# design.net
KiCad netlist of a schematic drawn in Altium Designer
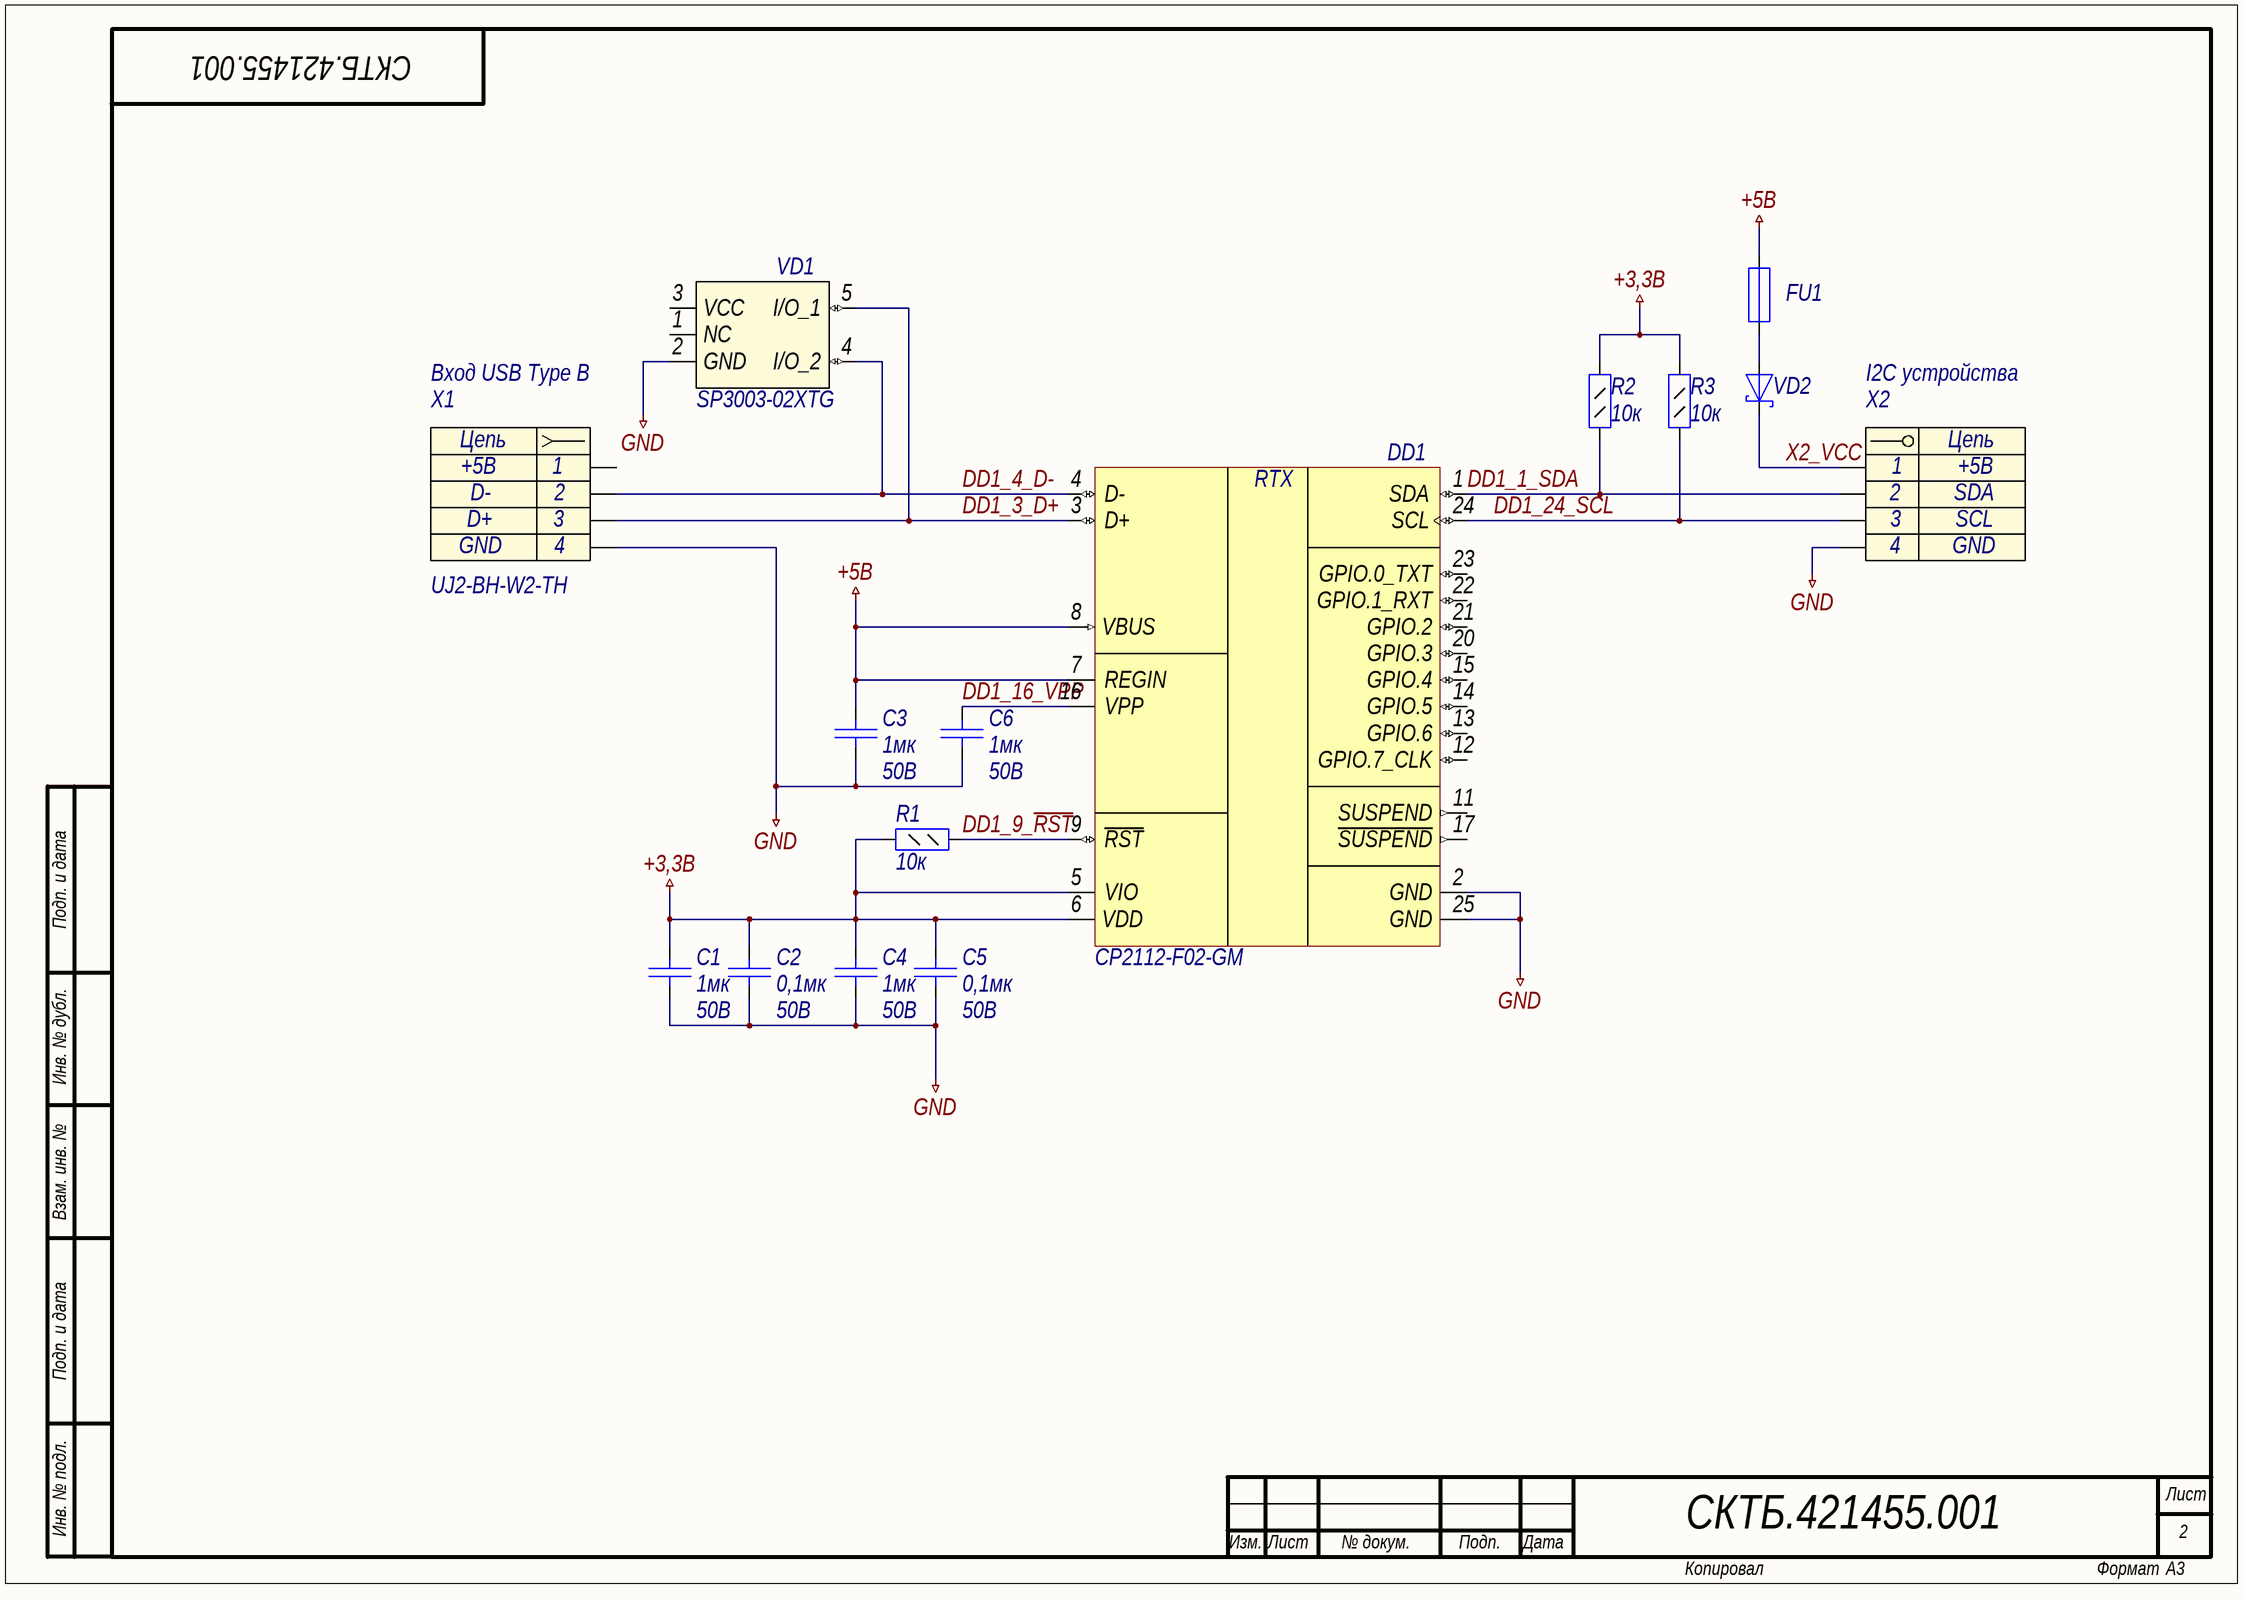
[diagram p0: Преобразователь интерфейсов.SchDoc]

(export (version "E")
  (design (tool "Eeschema 10.0.6"))
  (components
    (comp (ref "C1")
      (value "1мк")
      (footprint "C0603")
      (description "Конденсатор")
      (fields
        (field (name "VOLTAGE") "50B")
        (field (name "PART NUMBER") "GRM188R71C105KA12D**")
        (field (name "Comment") "Capacitor")
      )
      (libsource (lib "MOP44") (part "Capacitor"))
    )
    (comp (ref "C2")
      (value "0,1мк")
      (footprint "C0603")
      (description "Конденсатор")
      (fields
        (field (name "VOLTAGE") "50B")
        (field (name "PART NUMBER") "GRM188R71H104K")
        (field (name "Comment") "Capacitor")
      )
      (libsource (lib "MOP44") (part "Capacitor"))
    )
    (comp (ref "C3")
      (value "1мк")
      (footprint "C0603")
      (description "Конденсатор")
      (fields
        (field (name "VOLTAGE") "50B")
        (field (name "PART NUMBER") "GRM188R71C105KA12D**")
        (field (name "Comment") "Capacitor")
      )
      (libsource (lib "MOP44") (part "Capacitor"))
    )
    (comp (ref "C4")
      (value "1мк")
      (footprint "C0603")
      (description "Конденсатор")
      (fields
        (field (name "VOLTAGE") "50B")
        (field (name "PART NUMBER") "GRM188R71C105KA12D**")
        (field (name "Comment") "Capacitor")
      )
      (libsource (lib "MOP44") (part "Capacitor"))
    )
    (comp (ref "C5")
      (value "0,1мк")
      (footprint "C0603")
      (description "Конденсатор")
      (fields
        (field (name "VOLTAGE") "50B")
        (field (name "PART NUMBER") "GRM188R71H104K")
        (field (name "Comment") "Capacitor")
      )
      (libsource (lib "MOP44") (part "Capacitor"))
    )
    (comp (ref "C6")
      (value "1мк")
      (footprint "C0603")
      (description "Конденсатор")
      (fields
        (field (name "VOLTAGE") "50B")
        (field (name "PART NUMBER") "GRM188R71C105KA12D**")
        (field (name "Comment") "Capacitor")
      )
      (libsource (lib "MOP44") (part "Capacitor"))
    )
    (comp (ref "DD1")
      (value "CP2112-F02-GM")
      (footprint "QFN24")
      (description "USB-I2C преобразователь")
      (libsource (lib "MOP44") (part "CP2112-F02-GM"))
    )
    (comp (ref "FU1")
      (value "Fuse")
      (footprint "FUSE812")
      (description "Предохранитель")
      (fields (field (name "PART NUMBER") "MF-USMF005-2"))
      (libsource (lib "MOP44") (part "Fuse"))
    )
    (comp (ref "R1")
      (value "10к")
      (footprint "R0805")
      (description "Резистор")
      (fields (field (name "PART NUMBER") "RC0805FR-0710KL") (field (name "POWER") "0,125Вт"))
      (libsource (lib "MOP44") (part "Resistor_0,125Вт"))
    )
    (comp (ref "R2")
      (value "10к")
      (footprint "R0805")
      (description "Резистор")
      (fields (field (name "PART NUMBER") "RC0805FR-0710KL") (field (name "POWER") "0,125Вт"))
      (libsource (lib "") (part "Resistor_0,125Вт_1"))
    )
    (comp (ref "R3")
      (value "10к")
      (footprint "R0805")
      (description "Резистор")
      (fields (field (name "PART NUMBER") "RC0805FR-0710KL") (field (name "POWER") "0,125Вт"))
      (libsource (lib "") (part "Resistor_0,125Вт_1"))
    )
    (comp (ref "VD1")
      (value "SP3003-02XTG")
      (footprint "SOT553")
      (description "Двухканальная ESD защита USB")
      (libsource (lib "MOP44") (part "SP3003-02XTG"))
    )
    (comp (ref "VD2")
      (value "DiodeSchottky")
      (footprint "SMA")
      (description "Диод Шоттки")
      (fields (field (name "PART NUMBER") "SK34A"))
      (libsource (lib "MOP44") (part "DiodeSchottky"))
    )
    (comp (ref "X1")
      (value "Вход USB Type B")
      (footprint "USB-B RECEPTACLE")
      (description "Разъем - 4 конт. розетка")
      (fields (field (name "PART NUMBER") "UJ2-BH-W2-TH"))
      (libsource (lib "MOP44") (part "Header_4_sct"))
    )
    (comp (ref "X2")
      (value "I2C устройства")
      (footprint "TERMINAL 4 way-5mm")
      (description "Разъем - 4 конт. клеммник")
      (libsource (lib "MOP44") (part "Header_4_trm"))
    )
  )
  (nets
    (net (code "1") (name "+3,3В") (class "Default")
      (node (ref "C1") (pin "2") (pinfunction "2_2") (pintype "passive"))
      (node (ref "C2") (pin "2") (pinfunction "2_2") (pintype "passive"))
      (node (ref "C4") (pin "2") (pinfunction "2_2") (pintype "passive"))
      (node (ref "C5") (pin "2") (pinfunction "2_2") (pintype "passive"))
      (node (ref "DD1") (pin "5") (pinfunction "VIO_5") (pintype "power_in"))
      (node (ref "DD1") (pin "6") (pinfunction "VDD_6") (pintype "power_in"))
      (node (ref "R1") (pin "2") (pinfunction "2_2") (pintype "passive"))
      (node (ref "R2") (pin "2") (pinfunction "2_2") (pintype "passive"))
      (node (ref "R3") (pin "2") (pinfunction "2_2") (pintype "passive"))
    )
    (net (code "2") (name "+5В") (class "Default")
      (node (ref "C3") (pin "2") (pinfunction "2_2") (pintype "passive"))
      (node (ref "DD1") (pin "7") (pinfunction "REGIN_7") (pintype "power_in"))
      (node (ref "DD1") (pin "8") (pinfunction "VBUS_8") (pintype "input"))
      (node (ref "FU1") (pin "2") (pinfunction "2_2") (pintype "passive"))
    )
    (net (code "3") (name "/DD1_1_SDA") (class "Default")
      (node (ref "DD1") (pin "1") (pinfunction "SDA_1") (pintype "bidirectional"))
      (node (ref "R2") (pin "1") (pinfunction "1_1") (pintype "passive"))
      (node (ref "X2") (pin "2") (pinfunction "2_2") (pintype "passive"))
    )
    (net (code "4") (name "/DD1_3_D+") (class "Default")
      (node (ref "DD1") (pin "3") (pinfunction "D+_3") (pintype "bidirectional"))
      (node (ref "VD1") (pin "5") (pinfunction "I/O_1_5") (pintype "bidirectional"))
      (node (ref "X1") (pin "3") (pinfunction "3_3") (pintype "passive"))
    )
    (net (code "5") (name "/DD1_4_D-") (class "Default")
      (node (ref "DD1") (pin "4") (pinfunction "D-_4") (pintype "bidirectional"))
      (node (ref "VD1") (pin "4") (pinfunction "I/O_2_4") (pintype "bidirectional"))
      (node (ref "X1") (pin "2") (pinfunction "2_2") (pintype "passive"))
    )
    (net (code "6") (name "/DD1_9_~{RST}") (class "Default")
      (node (ref "DD1") (pin "9") (pinfunction "~{RST}_9") (pintype "bidirectional"))
      (node (ref "R1") (pin "1") (pinfunction "1_1") (pintype "passive"))
    )
    (net (code "7") (name "/DD1_16_VPP") (class "Default")
      (node (ref "C6") (pin "2") (pinfunction "2_2") (pintype "passive"))
      (node (ref "DD1") (pin "16") (pinfunction "VPP_16") (pintype "passive"))
    )
    (net (code "8") (name "/DD1_24_SCL") (class "Default")
      (node (ref "DD1") (pin "24") (pinfunction "SCL_24") (pintype "bidirectional"))
      (node (ref "R3") (pin "1") (pinfunction "1_1") (pintype "passive"))
      (node (ref "X2") (pin "3") (pinfunction "3_3") (pintype "passive"))
    )
    (net (code "9") (name "/X2_VCC") (class "Default")
      (node (ref "VD2") (pin "1") (pinfunction "K_1") (pintype "passive"))
      (node (ref "X2") (pin "1") (pinfunction "1_1") (pintype "passive"))
    )
    (net (code "10") (name "GND") (class "Default")
      (node (ref "C1") (pin "1") (pinfunction "1_1") (pintype "passive"))
      (node (ref "C2") (pin "1") (pinfunction "1_1") (pintype "passive"))
      (node (ref "C3") (pin "1") (pinfunction "1_1") (pintype "passive"))
      (node (ref "C4") (pin "1") (pinfunction "1_1") (pintype "passive"))
      (node (ref "C5") (pin "1") (pinfunction "1_1") (pintype "passive"))
      (node (ref "C6") (pin "1") (pinfunction "1_1") (pintype "passive"))
      (node (ref "DD1") (pin "2") (pinfunction "GND_2") (pintype "power_in"))
      (node (ref "DD1") (pin "25") (pinfunction "GND_25") (pintype "power_in"))
      (node (ref "VD1") (pin "2") (pinfunction "GND_2") (pintype "passive"))
      (node (ref "X1") (pin "4") (pinfunction "4_4") (pintype "passive"))
      (node (ref "X2") (pin "4") (pinfunction "4_4") (pintype "passive"))
    )
    (net (code "11") (name "Net-(VD2-A)") (class "Default")
      (node (ref "FU1") (pin "1") (pinfunction "1_1") (pintype "passive"))
      (node (ref "VD2") (pin "2") (pinfunction "A_2") (pintype "passive"))
    )
    (net (code "12") (name "unconnected-(DD1-GPIO.0_TXT-Pad23)") (class "Default")
      (node (ref "DD1") (pin "23") (pinfunction "GPIO.0_TXT_23") (pintype "bidirectional"))
    )
    (net (code "13") (name "unconnected-(DD1-GPIO.1_RXT-Pad22)") (class "Default")
      (node (ref "DD1") (pin "22") (pinfunction "GPIO.1_RXT_22") (pintype "bidirectional"))
    )
    (net (code "14") (name "unconnected-(DD1-GPIO.2-Pad21)") (class "Default")
      (node (ref "DD1") (pin "21") (pinfunction "GPIO.2_21") (pintype "bidirectional"))
    )
    (net (code "15") (name "unconnected-(DD1-GPIO.3-Pad20)") (class "Default")
      (node (ref "DD1") (pin "20") (pinfunction "GPIO.3_20") (pintype "bidirectional"))
    )
    (net (code "16") (name "unconnected-(DD1-GPIO.4-Pad15)") (class "Default")
      (node (ref "DD1") (pin "15") (pinfunction "GPIO.4_15") (pintype "bidirectional"))
    )
    (net (code "17") (name "unconnected-(DD1-GPIO.5-Pad14)") (class "Default")
      (node (ref "DD1") (pin "14") (pinfunction "GPIO.5_14") (pintype "bidirectional"))
    )
    (net (code "18") (name "unconnected-(DD1-GPIO.6-Pad13)") (class "Default")
      (node (ref "DD1") (pin "13") (pinfunction "GPIO.6_13") (pintype "bidirectional"))
    )
    (net (code "19") (name "unconnected-(DD1-GPIO.7_CLK-Pad12)") (class "Default")
      (node (ref "DD1") (pin "12") (pinfunction "GPIO.7_CLK_12") (pintype "bidirectional"))
    )
    (net (code "20") (name "unconnected-(DD1-SUSPEND-Pad11)") (class "Default")
      (node (ref "DD1") (pin "11") (pinfunction "SUSPEND_11") (pintype "output"))
    )
    (net (code "21") (name "unconnected-(DD1-~{SUSPEND}-Pad17)") (class "Default")
      (node (ref "DD1") (pin "17") (pinfunction "~{SUSPEND}_17") (pintype "output"))
    )
    (net (code "22") (name "unconnected-(VD1-NC-Pad1)") (class "Default")
      (node (ref "VD1") (pin "1") (pinfunction "NC_1") (pintype "passive"))
    )
    (net (code "23") (name "unconnected-(VD1-VCC-Pad3)") (class "Default")
      (node (ref "VD1") (pin "3") (pinfunction "VCC_3") (pintype "power_in"))
    )
    (net (code "24") (name "unconnected-(X1-Pad1)") (class "Default")
      (node (ref "X1") (pin "1") (pinfunction "1_1") (pintype "passive"))
    )
  )
)
